# device.net
KiCad netlist of a schematic drawn in EAGLE
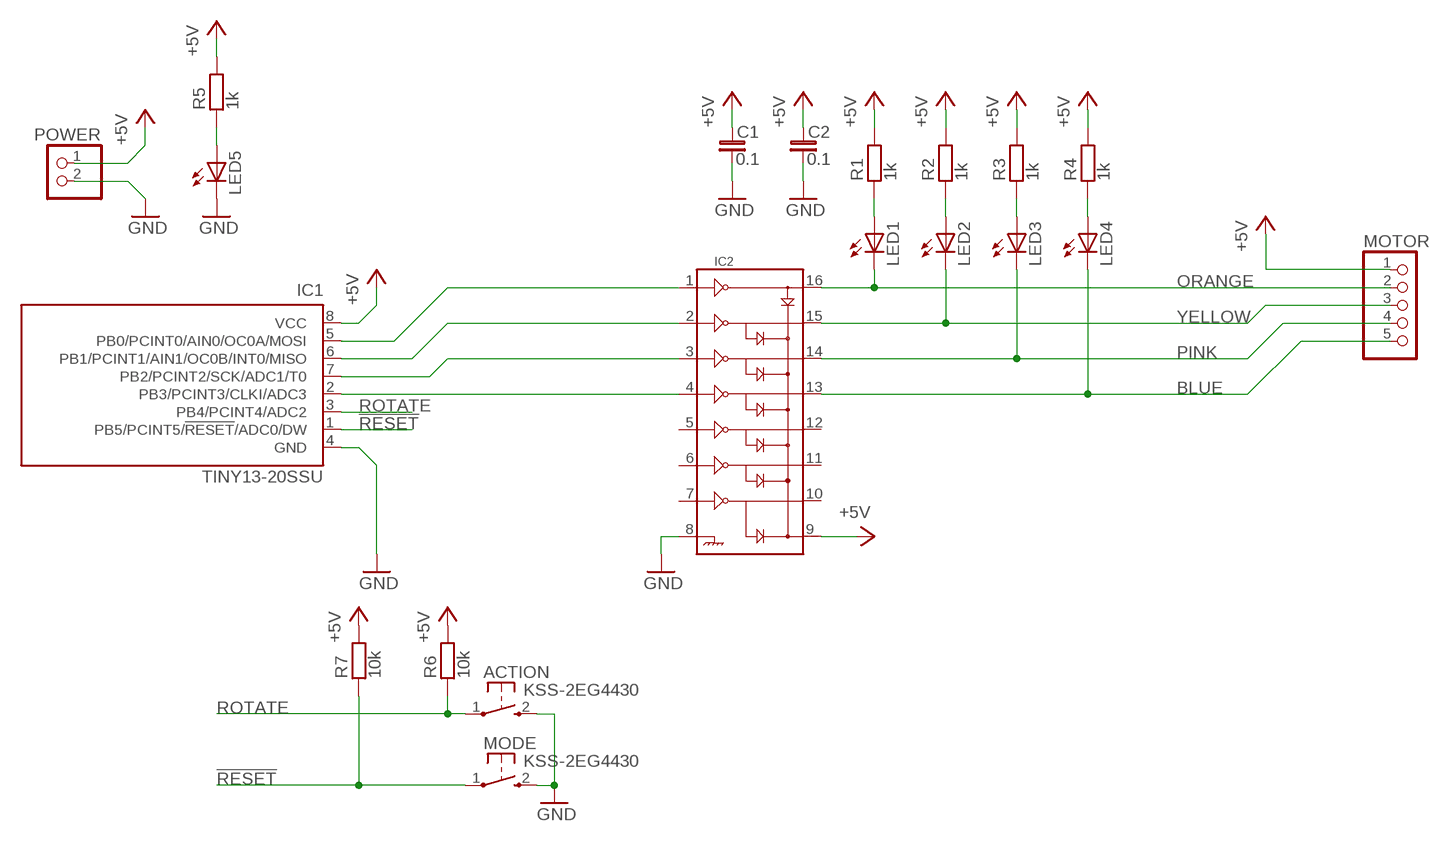
[diagram p0: schematic, sheet 1]

(export (version "E")
  (design (tool "Eeschema 10.0.6"))
  (components
    (comp (ref "ACTION")
      (value "KSS-2EG4430")
      (footprint "eagle-import:KSS-2EG4430")
      (libsource (lib "eagle-import") (part "KSS-2EG4430"))
    )
    (comp (ref "C1")
      (value "0.1")
      (footprint "eagle-import:C0805")
      (libsource (lib "eagle-import") (part "C_0805"))
    )
    (comp (ref "C2")
      (value "0.1")
      (footprint "eagle-import:C0805")
      (libsource (lib "eagle-import") (part "C_0805"))
    )
    (comp (ref "IC1")
      (value "TINY13-20SSU")
      (footprint "eagle-import:8S1")
      (libsource (lib "eagle-import") (part "TINY13SSU-20"))
    )
    (comp (ref "IC2")
      (value "ULN2003D")
      (footprint "eagle-import:SO16")
      (libsource (lib "eagle-import") (part "ULN2003D"))
    )
    (comp (ref "LED1")
      (value "LEDCHIPLED_0805")
      (footprint "eagle-import:CHIPLED_0805")
      (libsource (lib "eagle-import") (part "LEDCHIPLED_0805"))
    )
    (comp (ref "LED2")
      (value "LEDCHIPLED_0805")
      (footprint "eagle-import:CHIPLED_0805")
      (libsource (lib "eagle-import") (part "LEDCHIPLED_0805"))
    )
    (comp (ref "LED3")
      (value "LEDCHIPLED_0805")
      (footprint "eagle-import:CHIPLED_0805")
      (libsource (lib "eagle-import") (part "LEDCHIPLED_0805"))
    )
    (comp (ref "LED4")
      (value "LEDCHIPLED_0805")
      (footprint "eagle-import:CHIPLED_0805")
      (libsource (lib "eagle-import") (part "LEDCHIPLED_0805"))
    )
    (comp (ref "LED5")
      (value "LEDCHIPLED_0805")
      (footprint "eagle-import:CHIPLED_0805")
      (libsource (lib "eagle-import") (part "LEDCHIPLED_0805"))
    )
    (comp (ref "MODE")
      (value "KSS-2EG4430")
      (footprint "eagle-import:KSS-2EG4430")
      (libsource (lib "eagle-import") (part "KSS-2EG4430"))
    )
    (comp (ref "MOTOR")
      (value "PINHD-1X5_2.54")
      (footprint "eagle-import:1X05")
      (libsource (lib "eagle-import") (part "PINHD-1X5_2.54"))
    )
    (comp (ref "POWER")
      (value "PINHD-1X2_2.54")
      (footprint "eagle-import:1X02")
      (libsource (lib "eagle-import") (part "PINHD-1X2_2.54"))
    )
    (comp (ref "R1")
      (value "1k")
      (footprint "eagle-import:R0805")
      (libsource (lib "eagle-import") (part "R_0805"))
    )
    (comp (ref "R2")
      (value "1k")
      (footprint "eagle-import:R0805")
      (libsource (lib "eagle-import") (part "R_0805"))
    )
    (comp (ref "R3")
      (value "1k")
      (footprint "eagle-import:R0805")
      (libsource (lib "eagle-import") (part "R_0805"))
    )
    (comp (ref "R4")
      (value "1k")
      (footprint "eagle-import:R0805")
      (libsource (lib "eagle-import") (part "R_0805"))
    )
    (comp (ref "R5")
      (value "1k")
      (footprint "eagle-import:R0805")
      (libsource (lib "eagle-import") (part "R_0805"))
    )
    (comp (ref "R6")
      (value "10k")
      (footprint "eagle-import:R0805")
      (libsource (lib "eagle-import") (part "R_0805"))
    )
    (comp (ref "R7")
      (value "10k")
      (footprint "eagle-import:R0805")
      (libsource (lib "eagle-import") (part "R_0805"))
    )
  )
  (nets
    (net (code "1") (name "+5V") (class "Default")
      (node (ref "C1") (pin "1") (pinfunction "1_1") (pintype "passive"))
      (node (ref "C2") (pin "1") (pinfunction "1_1") (pintype "passive"))
      (node (ref "IC1") (pin "8") (pinfunction "VCC_8") (pintype "power_in"))
      (node (ref "IC2") (pin "9") (pinfunction "9_9") (pintype "power_in"))
      (node (ref "MOTOR") (pin "1") (pinfunction "1_1") (pintype "passive"))
      (node (ref "POWER") (pin "1") (pinfunction "1_1") (pintype "passive"))
      (node (ref "R1") (pin "2") (pinfunction "2_2") (pintype "passive"))
      (node (ref "R2") (pin "2") (pinfunction "2_2") (pintype "passive"))
      (node (ref "R3") (pin "2") (pinfunction "2_2") (pintype "passive"))
      (node (ref "R4") (pin "2") (pinfunction "2_2") (pintype "passive"))
      (node (ref "R5") (pin "2") (pinfunction "2_2") (pintype "passive"))
      (node (ref "R6") (pin "2") (pinfunction "2_2") (pintype "passive"))
      (node (ref "R7") (pin "2") (pinfunction "2_2") (pintype "passive"))
    )
    (net (code "2") (name "/BLUE") (class "Default")
      (node (ref "IC2") (pin "13") (pinfunction "13_13") (pintype "open_collector"))
      (node (ref "LED4") (pin "C") (pinfunction "C_C") (pintype "passive"))
      (node (ref "MOTOR") (pin "5") (pinfunction "5_5") (pintype "passive"))
    )
    (net (code "3") (name "/ORANGE") (class "Default")
      (node (ref "IC2") (pin "16") (pinfunction "16_16") (pintype "open_collector"))
      (node (ref "LED1") (pin "C") (pinfunction "C_C") (pintype "passive"))
      (node (ref "MOTOR") (pin "2") (pinfunction "2_2") (pintype "passive"))
    )
    (net (code "4") (name "/PINK") (class "Default")
      (node (ref "IC2") (pin "14") (pinfunction "14_14") (pintype "open_collector"))
      (node (ref "LED3") (pin "C") (pinfunction "C_C") (pintype "passive"))
      (node (ref "MOTOR") (pin "4") (pinfunction "4_4") (pintype "passive"))
    )
    (net (code "5") (name "/ROTATE") (class "Default")
      (node (ref "ACTION") (pin "1") (pinfunction "P_1") (pintype "passive"))
      (node (ref "IC1") (pin "3") (pinfunction "PB4/PCINT4/ADC2_3") (pintype "bidirectional"))
      (node (ref "R6") (pin "1") (pinfunction "1_1") (pintype "passive"))
    )
    (net (code "6") (name "/YELLOW") (class "Default")
      (node (ref "IC2") (pin "15") (pinfunction "15_15") (pintype "open_collector"))
      (node (ref "LED2") (pin "C") (pinfunction "C_C") (pintype "passive"))
      (node (ref "MOTOR") (pin "3") (pinfunction "3_3") (pintype "passive"))
    )
    (net (code "7") (name "/~{RESET}") (class "Default")
      (node (ref "IC1") (pin "1") (pinfunction "PB5/PCINT5/~{RESET}/ADC0/DW_1") (pintype "bidirectional"))
      (node (ref "MODE") (pin "1") (pinfunction "P_1") (pintype "passive"))
      (node (ref "R7") (pin "1") (pinfunction "1_1") (pintype "passive"))
    )
    (net (code "8") (name "GND") (class "Default")
      (node (ref "ACTION") (pin "2") (pinfunction "S_2") (pintype "passive"))
      (node (ref "C1") (pin "2") (pinfunction "2_2") (pintype "passive"))
      (node (ref "C2") (pin "2") (pinfunction "2_2") (pintype "passive"))
      (node (ref "IC1") (pin "4") (pinfunction "GND_4") (pintype "power_in"))
      (node (ref "IC2") (pin "8") (pinfunction "8_8") (pintype "power_in"))
      (node (ref "LED5") (pin "C") (pinfunction "C_C") (pintype "passive"))
      (node (ref "MODE") (pin "2") (pinfunction "S_2") (pintype "passive"))
      (node (ref "POWER") (pin "2") (pinfunction "2_2") (pintype "passive"))
    )
    (net (code "9") (name "Net-(IC1-PB0{slash}PCINT0{slash}AIN0{slash}OC0A{slash}MOSI)") (class "Default")
      (node (ref "IC1") (pin "5") (pinfunction "PB0/PCINT0/AIN0/OC0A/MOSI_5") (pintype "bidirectional"))
      (node (ref "IC2") (pin "1") (pinfunction "1_1") (pintype "input"))
    )
    (net (code "10") (name "Net-(IC1-PB1{slash}PCINT1{slash}AIN1{slash}OC0B{slash}INT0{slash}MISO)") (class "Default")
      (node (ref "IC1") (pin "6") (pinfunction "PB1/PCINT1/AIN1/OC0B/INT0/MISO_6") (pintype "bidirectional"))
      (node (ref "IC2") (pin "2") (pinfunction "2_2") (pintype "input"))
    )
    (net (code "11") (name "Net-(IC1-PB2{slash}PCINT2{slash}SCK{slash}ADC1{slash}T0)") (class "Default")
      (node (ref "IC1") (pin "7") (pinfunction "PB2/PCINT2/SCK/ADC1/T0_7") (pintype "bidirectional"))
      (node (ref "IC2") (pin "3") (pinfunction "3_3") (pintype "input"))
    )
    (net (code "12") (name "Net-(IC1-PB3{slash}PCINT3{slash}CLKI{slash}ADC3)") (class "Default")
      (node (ref "IC1") (pin "2") (pinfunction "PB3/PCINT3/CLKI/ADC3_2") (pintype "bidirectional"))
      (node (ref "IC2") (pin "4") (pinfunction "4_4") (pintype "input"))
    )
    (net (code "13") (name "Net-(LED1-PadA)") (class "Default")
      (node (ref "LED1") (pin "A") (pinfunction "A_A") (pintype "passive"))
      (node (ref "R1") (pin "1") (pinfunction "1_1") (pintype "passive"))
    )
    (net (code "14") (name "Net-(LED2-PadA)") (class "Default")
      (node (ref "LED2") (pin "A") (pinfunction "A_A") (pintype "passive"))
      (node (ref "R2") (pin "1") (pinfunction "1_1") (pintype "passive"))
    )
    (net (code "15") (name "Net-(LED3-PadA)") (class "Default")
      (node (ref "LED3") (pin "A") (pinfunction "A_A") (pintype "passive"))
      (node (ref "R3") (pin "1") (pinfunction "1_1") (pintype "passive"))
    )
    (net (code "16") (name "Net-(LED4-PadA)") (class "Default")
      (node (ref "LED4") (pin "A") (pinfunction "A_A") (pintype "passive"))
      (node (ref "R4") (pin "1") (pinfunction "1_1") (pintype "passive"))
    )
    (net (code "17") (name "Net-(LED5-PadA)") (class "Default")
      (node (ref "LED5") (pin "A") (pinfunction "A_A") (pintype "passive"))
      (node (ref "R5") (pin "1") (pinfunction "1_1") (pintype "passive"))
    )
    (net (code "18") (name "unconnected-(IC2-Pad5)") (class "Default")
      (node (ref "IC2") (pin "5") (pinfunction "5_5") (pintype "input"))
    )
    (net (code "19") (name "unconnected-(IC2-Pad6)") (class "Default")
      (node (ref "IC2") (pin "6") (pinfunction "6_6") (pintype "input"))
    )
    (net (code "20") (name "unconnected-(IC2-Pad7)") (class "Default")
      (node (ref "IC2") (pin "7") (pinfunction "7_7") (pintype "input"))
    )
    (net (code "21") (name "unconnected-(IC2-Pad10)") (class "Default")
      (node (ref "IC2") (pin "10") (pinfunction "10_10") (pintype "open_collector"))
    )
    (net (code "22") (name "unconnected-(IC2-Pad11)") (class "Default")
      (node (ref "IC2") (pin "11") (pinfunction "11_11") (pintype "open_collector"))
    )
    (net (code "23") (name "unconnected-(IC2-Pad12)") (class "Default")
      (node (ref "IC2") (pin "12") (pinfunction "12_12") (pintype "open_collector"))
    )
  )
)
